# peripherals.net
KiCad netlist of a schematic drawn in Altium Designer
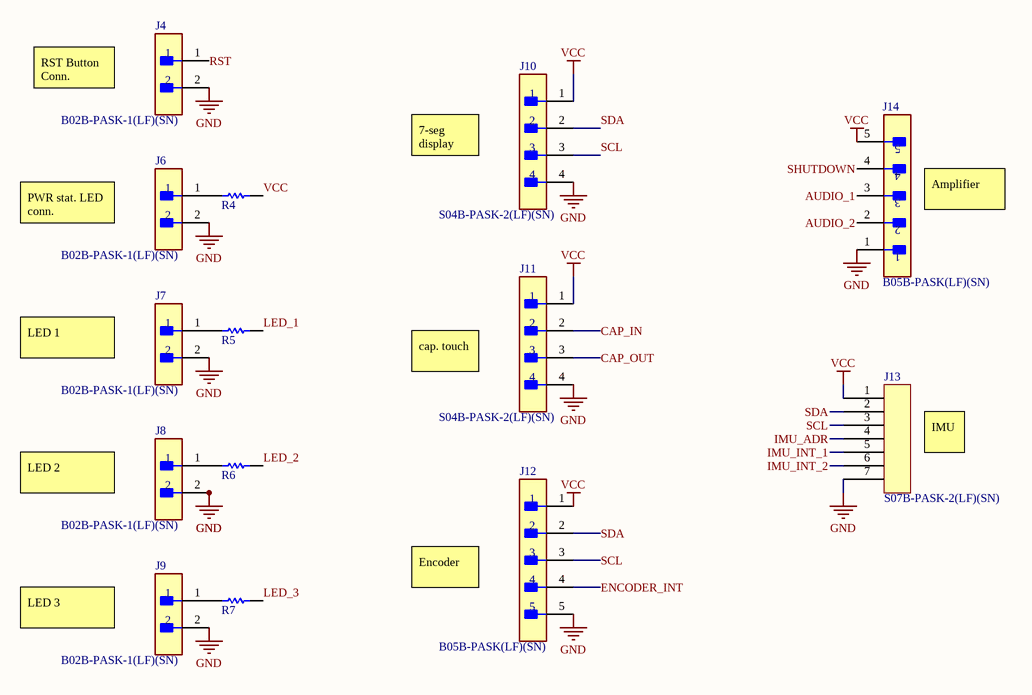
[diagram p0: peripherals.SchDoc]

(export (version "E")
  (design (tool "Eeschema 10.0.6"))
  (components
    (comp (ref "J4")
      (value "B02B-PASK-1(LF)(SN)")
      (footprint "FP-B02B-PASK-1_LF_SN-MFG")
      (description "CONN HEADER VERT 2POS 2MM")
      (libsource (lib "Altium Content Vault") (part "3bc925449376181038e59eaffc5286c"))
    )
    (comp (ref "J6")
      (value "B02B-PASK-1(LF)(SN)")
      (footprint "FP-B02B-PASK-1_LF_SN-MFG")
      (description "CONN HEADER VERT 2POS 2MM")
      (libsource (lib "Altium Content Vault") (part "3bc925449376181038e59eaffc5286c"))
    )
    (comp (ref "J7")
      (value "B02B-PASK-1(LF)(SN)")
      (footprint "FP-B02B-PASK-1_LF_SN-MFG")
      (description "CONN HEADER VERT 2POS 2MM")
      (libsource (lib "Altium Content Vault") (part "3bc925449376181038e59eaffc5286c"))
    )
    (comp (ref "J8")
      (value "B02B-PASK-1(LF)(SN)")
      (footprint "FP-B02B-PASK-1_LF_SN-MFG")
      (description "CONN HEADER VERT 2POS 2MM")
      (libsource (lib "Altium Content Vault") (part "3bc925449376181038e59eaffc5286c"))
    )
    (comp (ref "J9")
      (value "B02B-PASK-1(LF)(SN)")
      (footprint "FP-B02B-PASK-1_LF_SN-MFG")
      (description "CONN HEADER VERT 2POS 2MM")
      (libsource (lib "Altium Content Vault") (part "3bc925449376181038e59eaffc5286c"))
    )
    (comp (ref "J10")
      (value "S04B-PASK-2(LF)(SN)")
      (footprint "FP-S04B-PASK-2_LF_SN-MFG")
      (description "CONN HEADER R/A 4POS 2MM")
      (libsource (lib "Altium Content Vault") (part "299a8cea1bdcbc3624fe62c390fa72c"))
    )
    (comp (ref "J11")
      (value "S04B-PASK-2(LF)(SN)")
      (footprint "FP-S04B-PASK-2_LF_SN-MFG")
      (description "CONN HEADER R/A 4POS 2MM")
      (libsource (lib "Altium Content Vault") (part "299a8cea1bdcbc3624fe62c390fa72c"))
    )
    (comp (ref "J12")
      (value "B05B-PASK(LF)(SN)")
      (footprint "FP-B05B-PASK_LF_SN-MFG")
      (description "CONN HEADER VERT 5POS 2MM")
      (libsource (lib "Altium Content Vault") (part "bf93c07fd2649a848d0ec8585582aab"))
    )
    (comp (ref "J13")
      (value "S07B-PASK-2(LF)(SN)")
      (footprint "S07B-PASK-2(LF)(SN)-Footprint-1")
      (description "Conn Shrouded Header HDR 7 POS 2mm Solder RA Thru-Hole Box")
      (libsource (lib "University of Pittsburgh") (part "S07B-PASK-2(LF)(SN)-Symbol-1"))
    )
    (comp (ref "J14")
      (value "B05B-PASK(LF)(SN)")
      (footprint "FP-B05B-PASK_LF_SN-MFG")
      (description "CONN HEADER VERT 5POS 2MM")
      (libsource (lib "") (part "bf93c07fd2649a848d0ec8585582aab_1"))
    )
    (comp (ref "R4")
      (value "1k Through-Hole 1/4W")
      (footprint "RESA60-630X240")
      (description "RES 1K OHM 1/4W 1% AXIAL")
      (fields (field (name "TOLERANCE") "1%"))
      (libsource (lib "University of Pittsburgh") (part "RES-2"))
    )
    (comp (ref "R5")
      (value "1k Through-Hole 1/4W")
      (footprint "RESA60-630X240")
      (description "RES 1K OHM 1/4W 1% AXIAL")
      (fields (field (name "TOLERANCE") "1%"))
      (libsource (lib "University of Pittsburgh") (part "RES-2"))
    )
    (comp (ref "R6")
      (value "1k Through-Hole 1/4W")
      (footprint "RESA60-630X240")
      (description "RES 1K OHM 1/4W 1% AXIAL")
      (fields (field (name "TOLERANCE") "1%"))
      (libsource (lib "University of Pittsburgh") (part "RES-2"))
    )
    (comp (ref "R7")
      (value "1k Through-Hole 1/4W")
      (footprint "RESA60-630X240")
      (description "RES 1K OHM 1/4W 1% AXIAL")
      (fields (field (name "TOLERANCE") "1%"))
      (libsource (lib "University of Pittsburgh") (part "RES-2"))
    )
  )
  (nets
    (net (code "1") (name "/AUDIO_1") (class "Default")
      (node (ref "J14") (pin "3") (pinfunction "3_3") (pintype "passive"))
    )
    (net (code "2") (name "/AUDIO_2") (class "Default")
      (node (ref "J14") (pin "2") (pinfunction "2_2") (pintype "passive"))
    )
    (net (code "3") (name "/CAP_IN") (class "Default")
      (node (ref "J11") (pin "2") (pinfunction "2_2") (pintype "passive"))
    )
    (net (code "4") (name "/CAP_OUT") (class "Default")
      (node (ref "J11") (pin "3") (pinfunction "3_3") (pintype "passive"))
    )
    (net (code "5") (name "/ENCODER_INT") (class "Default")
      (node (ref "J12") (pin "4") (pinfunction "4_4") (pintype "passive"))
    )
    (net (code "6") (name "/IMU_ADR") (class "Default") (node (ref "J13") (pin "4") (pintype "passive")))
    (net (code "7") (name "/IMU_INT_1") (class "Default") (node (ref "J13") (pin "5") (pintype "passive")))
    (net (code "8") (name "/IMU_INT_2") (class "Default") (node (ref "J13") (pin "6") (pintype "passive")))
    (net (code "9") (name "/LED_1") (class "Default")
      (node (ref "R5") (pin "2") (pinfunction "2_2") (pintype "passive"))
    )
    (net (code "10") (name "/LED_2") (class "Default")
      (node (ref "R6") (pin "2") (pinfunction "2_2") (pintype "passive"))
    )
    (net (code "11") (name "/LED_3") (class "Default")
      (node (ref "R7") (pin "2") (pinfunction "2_2") (pintype "passive"))
    )
    (net (code "12") (name "/RST") (class "Default")
      (node (ref "J4") (pin "1") (pinfunction "1_1") (pintype "passive"))
    )
    (net (code "13") (name "/SCL") (class "Default")
      (node (ref "J10") (pin "3") (pinfunction "3_3") (pintype "passive"))
      (node (ref "J12") (pin "3") (pinfunction "3_3") (pintype "passive"))
      (node (ref "J13") (pin "3") (pintype "passive"))
    )
    (net (code "14") (name "/SDA") (class "Default")
      (node (ref "J10") (pin "2") (pinfunction "2_2") (pintype "passive"))
      (node (ref "J12") (pin "2") (pinfunction "2_2") (pintype "passive"))
      (node (ref "J13") (pin "2") (pintype "passive"))
    )
    (net (code "15") (name "/SHUTDOWN") (class "Default")
      (node (ref "J14") (pin "4") (pinfunction "4_4") (pintype "passive"))
    )
    (net (code "16") (name "GND") (class "Default")
      (node (ref "J10") (pin "4") (pinfunction "4_4") (pintype "passive"))
      (node (ref "J11") (pin "4") (pinfunction "4_4") (pintype "passive"))
      (node (ref "J12") (pin "5") (pinfunction "5_5") (pintype "passive"))
      (node (ref "J13") (pin "7") (pintype "passive"))
      (node (ref "J14") (pin "1") (pinfunction "1_1") (pintype "passive"))
      (node (ref "J4") (pin "2") (pinfunction "2_2") (pintype "passive"))
      (node (ref "J6") (pin "2") (pinfunction "2_2") (pintype "passive"))
      (node (ref "J7") (pin "2") (pinfunction "2_2") (pintype "passive"))
      (node (ref "J8") (pin "2") (pinfunction "2_2") (pintype "passive"))
      (node (ref "J9") (pin "2") (pinfunction "2_2") (pintype "passive"))
    )
    (net (code "17") (name "Net-(J6-Pad1)") (class "Default")
      (node (ref "J6") (pin "1") (pinfunction "1_1") (pintype "passive"))
      (node (ref "R4") (pin "1") (pinfunction "1_1") (pintype "passive"))
    )
    (net (code "18") (name "Net-(J7-Pad1)") (class "Default")
      (node (ref "J7") (pin "1") (pinfunction "1_1") (pintype "passive"))
      (node (ref "R5") (pin "1") (pinfunction "1_1") (pintype "passive"))
    )
    (net (code "19") (name "Net-(J8-Pad1)") (class "Default")
      (node (ref "J8") (pin "1") (pinfunction "1_1") (pintype "passive"))
      (node (ref "R6") (pin "1") (pinfunction "1_1") (pintype "passive"))
    )
    (net (code "20") (name "Net-(J9-Pad1)") (class "Default")
      (node (ref "J9") (pin "1") (pinfunction "1_1") (pintype "passive"))
      (node (ref "R7") (pin "1") (pinfunction "1_1") (pintype "passive"))
    )
    (net (code "21") (name "VCC") (class "Default")
      (node (ref "J10") (pin "1") (pinfunction "1_1") (pintype "passive"))
      (node (ref "J11") (pin "1") (pinfunction "1_1") (pintype "passive"))
      (node (ref "J12") (pin "1") (pinfunction "1_1") (pintype "passive"))
      (node (ref "J13") (pin "1") (pintype "passive"))
      (node (ref "J14") (pin "5") (pinfunction "5_5") (pintype "passive"))
      (node (ref "R4") (pin "2") (pinfunction "2_2") (pintype "passive"))
    )
  )
)
